# OEMV1_GPS_Interface.net
KiCad netlist of a schematic drawn in EAGLE
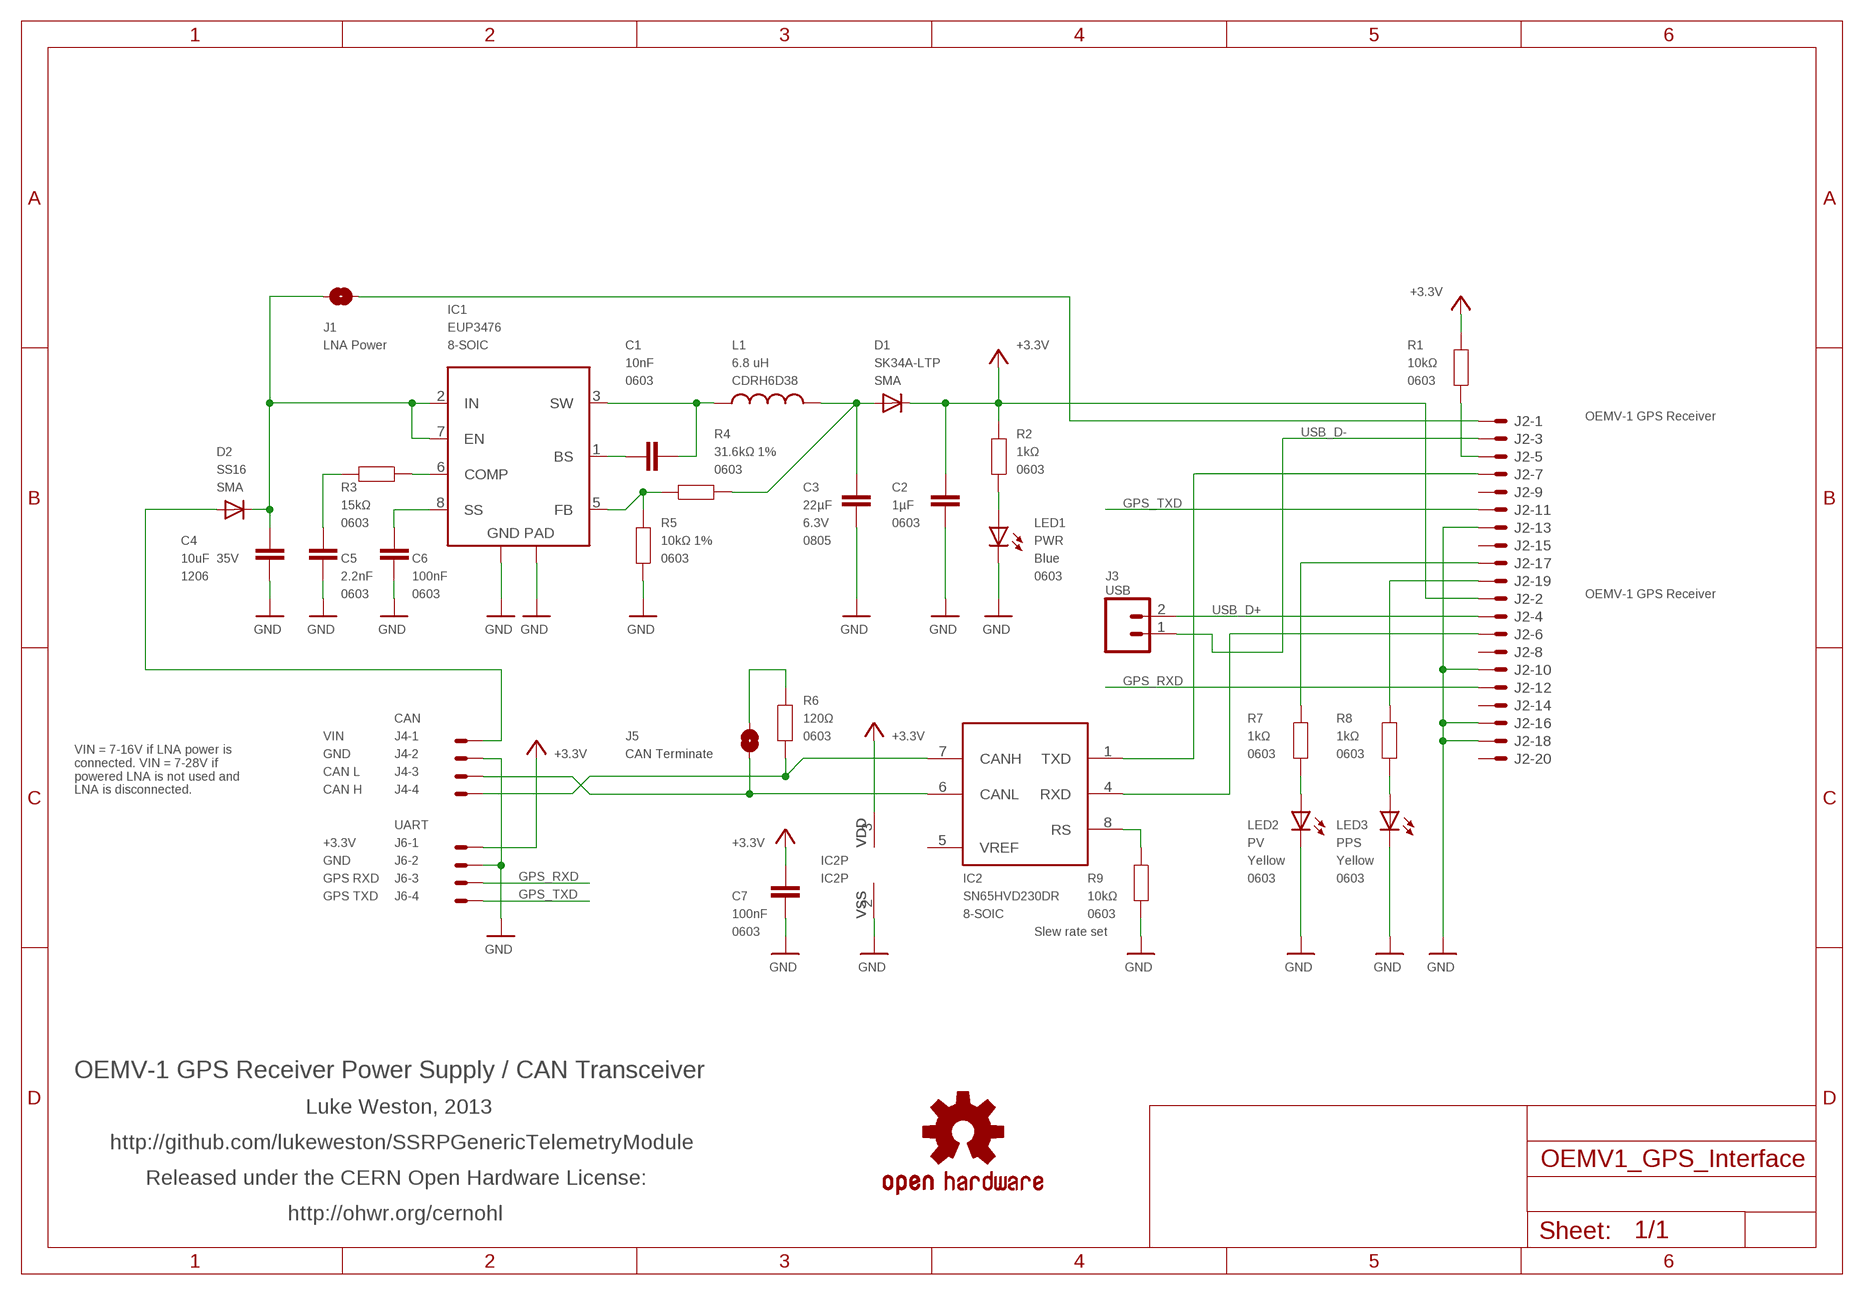
[diagram p0: schematic, sheet 1]

(export (version "E")
  (design (tool "Eeschema 10.0.6"))
  (components
    (comp (ref "C1")
      (value "10nF")
      (footprint "eagle-import:0603")
      (fields (field (name "PACKAGE") "0603"))
      (libsource (lib "eagle-import") (part "CAP0603"))
    )
    (comp (ref "C2")
      (value "1µF")
      (footprint "eagle-import:0603")
      (fields (field (name "PACKAGE") "0603"))
      (libsource (lib "eagle-import") (part "CAP0603"))
    )
    (comp (ref "C3")
      (value "22µF")
      (footprint "eagle-import:0805")
      (fields (field (name "PACKAGE") "0805") (field (name "VOLTAGE") "6.3V"))
      (libsource (lib "eagle-import") (part "CAP0805"))
    )
    (comp (ref "C4")
      (value "10uF")
      (footprint "eagle-import:C1206")
      (fields (field (name "PACKAGE") "1206") (field (name "VOLTAGE") "35V"))
      (libsource (lib "eagle-import") (part "C-EUC1206"))
    )
    (comp (ref "C5")
      (value "2.2nF")
      (footprint "eagle-import:0603")
      (fields (field (name "PACKAGE") "0603"))
      (libsource (lib "eagle-import") (part "CAP0603"))
    )
    (comp (ref "C6")
      (value "100nF")
      (footprint "eagle-import:0603")
      (fields (field (name "PACKAGE") "0603"))
      (libsource (lib "eagle-import") (part "CAP0603"))
    )
    (comp (ref "C7")
      (value "100nF")
      (footprint "eagle-import:0603")
      (fields (field (name "PACKAGE") "0603"))
      (libsource (lib "eagle-import") (part "CAP0603"))
    )
    (comp (ref "D1")
      (value "SK34A-LTP")
      (footprint "eagle-import:SMA-DIODE")
      (fields (field (name "PACKAGE") "SMA"))
      (libsource (lib "eagle-import") (part "DIODESMA"))
    )
    (comp (ref "D2")
      (value "SS16")
      (footprint "eagle-import:SMA-DIODE")
      (fields (field (name "PACKAGE") "SMA"))
      (libsource (lib "eagle-import") (part "DIODESMA"))
    )
    (comp (ref "IC1")
      (value "EUP3476")
      (footprint "eagle-import:SO08T")
      (fields (field (name "PACKAGE") "8-SOIC"))
      (libsource (lib "eagle-import") (part "EUP3476"))
    )
    (comp (ref "IC2")
      (value "SN65HVD230DR")
      (footprint "eagle-import:SO-08")
      (fields (field (name "PACKAGE") "8-SOIC"))
      (libsource (lib "eagle-import") (part "MCP2551SN"))
    )
    (comp (ref "J1")
      (value "LNA Power")
      (footprint "eagle-import:SJ")
      (libsource (lib "eagle-import") (part "SJ"))
    )
    (comp (ref "J2")
      (value "OEMV-1 GPS Receiver")
      (footprint "eagle-import:87758-2016")
      (fields (field (name "MPN") "87758-2016"))
      (libsource (lib "eagle-import") (part "87758-2016"))
    )
    (comp (ref "J3")
      (value "USB")
      (footprint "eagle-import:1X02")
      (libsource (lib "eagle-import") (part "M02PTH"))
    )
    (comp (ref "J4")
      (value "CAN")
      (footprint "eagle-import:22-23-2041")
      (fields (field (name "MF") "MOLEX") (field (name "MPN") "22-23-2041"))
      (libsource (lib "eagle-import") (part "22-23-2041"))
    )
    (comp (ref "J5")
      (value "CAN Terminate")
      (footprint "eagle-import:SJ")
      (libsource (lib "eagle-import") (part "SJ"))
    )
    (comp (ref "J6")
      (value "UART")
      (footprint "eagle-import:22-23-2041")
      (fields (field (name "MF") "MOLEX") (field (name "MPN") "22-23-2041"))
      (libsource (lib "eagle-import") (part "22-23-2041"))
    )
    (comp (ref "L1")
      (value "6.8 uH")
      (footprint "eagle-import:CDRH")
      (fields (field (name "SKU") "CDRH6D38"))
      (libsource (lib "eagle-import") (part "INDUCTOR"))
    )
    (comp (ref "LED1")
      (value "PWR")
      (footprint "eagle-import:LED-0603")
      (fields (field (name "COLOUR") "Blue") (field (name "PACKAGE") "0603"))
      (libsource (lib "eagle-import") (part "LED0603"))
    )
    (comp (ref "LED2")
      (value "PV")
      (footprint "eagle-import:LED-0603")
      (fields (field (name "COLOUR") "Yellow") (field (name "PACKAGE") "0603"))
      (libsource (lib "eagle-import") (part "LED0603"))
    )
    (comp (ref "LED3")
      (value "PPS")
      (footprint "eagle-import:LED-0603")
      (fields (field (name "COLOUR") "Yellow") (field (name "PACKAGE") "0603"))
      (libsource (lib "eagle-import") (part "LED0603"))
    )
    (comp (ref "R1")
      (value "10kΩ")
      (footprint "eagle-import:0603")
      (fields (field (name "PACKAGE") "0603"))
      (libsource (lib "eagle-import") (part "RESISTOR0603"))
    )
    (comp (ref "R2")
      (value "1kΩ")
      (footprint "eagle-import:0603")
      (fields (field (name "PACKAGE") "0603"))
      (libsource (lib "eagle-import") (part "RESISTOR0603"))
    )
    (comp (ref "R3")
      (value "15kΩ")
      (footprint "eagle-import:0603")
      (fields (field (name "PACKAGE") "0603"))
      (libsource (lib "eagle-import") (part "RESISTOR0603"))
    )
    (comp (ref "R4")
      (value "31.6kΩ 1%")
      (footprint "eagle-import:0603")
      (fields (field (name "PACKAGE") "0603"))
      (libsource (lib "eagle-import") (part "RESISTOR0603"))
    )
    (comp (ref "R5")
      (value "10kΩ 1%")
      (footprint "eagle-import:0603")
      (fields (field (name "PACKAGE") "0603"))
      (libsource (lib "eagle-import") (part "RESISTOR0603"))
    )
    (comp (ref "R6")
      (value "120Ω")
      (footprint "eagle-import:0603")
      (fields (field (name "PACKAGE") "0603"))
      (libsource (lib "eagle-import") (part "RESISTOR0603"))
    )
    (comp (ref "R7")
      (value "1kΩ")
      (footprint "eagle-import:0603")
      (fields (field (name "PACKAGE") "0603"))
      (libsource (lib "eagle-import") (part "RESISTOR0603"))
    )
    (comp (ref "R8")
      (value "1kΩ")
      (footprint "eagle-import:0603")
      (fields (field (name "PACKAGE") "0603"))
      (libsource (lib "eagle-import") (part "RESISTOR0603"))
    )
    (comp (ref "R9")
      (value "10kΩ")
      (footprint "eagle-import:0603")
      (fields (field (name "FUNCTION") "Slew rate set") (field (name "PACKAGE") "0603"))
      (libsource (lib "eagle-import") (part "RESISTOR0603"))
    )
    (comp (ref "SY")
      (value "OSHW-LOGOS")
      (footprint "eagle-import:OSHW-LOGO-S")
      (libsource (lib "eagle-import") (part "OSHW-LOGOS"))
    )
  )
  (nets
    (net (code "1") (name "+3.3V") (class "Default")
      (node (ref "C2") (pin "2") (pinfunction "2_2") (pintype "passive"))
      (node (ref "C7") (pin "2") (pinfunction "2_2") (pintype "passive"))
      (node (ref "D1") (pin "C") (pinfunction "C_C") (pintype "passive"))
      (node (ref "IC2") (pin "3") (pinfunction "VDD_3") (pintype "power_in"))
      (node (ref "J2") (pin "2") (pinfunction "S_2") (pintype "passive"))
      (node (ref "J6") (pin "1") (pinfunction "S_1") (pintype "passive"))
      (node (ref "R1") (pin "1") (pinfunction "1_1") (pintype "passive"))
      (node (ref "R2") (pin "1") (pinfunction "1_1") (pintype "passive"))
    )
    (net (code "2") (name "/GPS_RXD") (class "Default")
      (node (ref "J2") (pin "12") (pinfunction "S_12") (pintype "passive"))
      (node (ref "J6") (pin "3") (pinfunction "S_3") (pintype "passive"))
    )
    (net (code "3") (name "/GPS_TXD") (class "Default")
      (node (ref "J2") (pin "11") (pinfunction "S_11") (pintype "passive"))
      (node (ref "J6") (pin "4") (pinfunction "S_4") (pintype "passive"))
    )
    (net (code "4") (name "/USB_D+") (class "Default")
      (node (ref "J2") (pin "4") (pinfunction "S_4") (pintype "passive"))
      (node (ref "J3") (pin "2") (pinfunction "2_2") (pintype "passive"))
    )
    (net (code "5") (name "/USB_D-") (class "Default")
      (node (ref "J2") (pin "3") (pinfunction "S_3") (pintype "passive"))
      (node (ref "J3") (pin "1") (pinfunction "1_1") (pintype "passive"))
    )
    (net (code "6") (name "/VREF") (class "Default")
      (node (ref "IC2") (pin "5") (pinfunction "VREF_5") (pintype "power_in"))
    )
    (net (code "7") (name "GND") (class "Default")
      (node (ref "C2") (pin "1") (pinfunction "1_1") (pintype "passive"))
      (node (ref "C3") (pin "2") (pinfunction "2_2") (pintype "passive"))
      (node (ref "C4") (pin "2") (pinfunction "2_2") (pintype "passive"))
      (node (ref "C5") (pin "1") (pinfunction "1_1") (pintype "passive"))
      (node (ref "C6") (pin "1") (pinfunction "1_1") (pintype "passive"))
      (node (ref "C7") (pin "1") (pinfunction "1_1") (pintype "passive"))
      (node (ref "IC1") (pin "4") (pinfunction "GND_4") (pintype "power_in"))
      (node (ref "IC1") (pin "9") (pinfunction "TGND_9") (pintype "power_in"))
      (node (ref "IC2") (pin "2") (pinfunction "VSS_2") (pintype "power_in"))
      (node (ref "J2") (pin "10") (pinfunction "S_10") (pintype "passive"))
      (node (ref "J2") (pin "13") (pinfunction "S_13") (pintype "passive"))
      (node (ref "J2") (pin "16") (pinfunction "S_16") (pintype "passive"))
      (node (ref "J2") (pin "18") (pinfunction "S_18") (pintype "passive"))
      (node (ref "J4") (pin "2") (pinfunction "S_2") (pintype "passive"))
      (node (ref "J6") (pin "2") (pinfunction "S_2") (pintype "passive"))
      (node (ref "LED1") (pin "C") (pinfunction "C_C") (pintype "passive"))
      (node (ref "LED2") (pin "C") (pinfunction "C_C") (pintype "passive"))
      (node (ref "LED3") (pin "C") (pinfunction "C_C") (pintype "passive"))
      (node (ref "R5") (pin "2") (pinfunction "2_2") (pintype "passive"))
      (node (ref "R9") (pin "2") (pinfunction "2_2") (pintype "passive"))
    )
    (net (code "8") (name "Net-(C3-Pad1)") (class "Default")
      (node (ref "C3") (pin "1") (pinfunction "1_1") (pintype "passive"))
      (node (ref "D1") (pin "A") (pinfunction "A_A") (pintype "passive"))
      (node (ref "L1") (pin "2") (pinfunction "2_2") (pintype "bidirectional"))
      (node (ref "R4") (pin "2") (pinfunction "2_2") (pintype "passive"))
    )
    (net (code "9") (name "Net-(C5-Pad2)") (class "Default")
      (node (ref "C5") (pin "2") (pinfunction "2_2") (pintype "passive"))
      (node (ref "R3") (pin "2") (pinfunction "2_2") (pintype "passive"))
    )
    (net (code "10") (name "Net-(IC1-BS)") (class "Default")
      (node (ref "C1") (pin "2") (pinfunction "2_2") (pintype "passive"))
      (node (ref "IC1") (pin "1") (pinfunction "BS_1") (pintype "bidirectional"))
    )
    (net (code "11") (name "Net-(IC1-COMP)") (class "Default")
      (node (ref "IC1") (pin "6") (pinfunction "COMP_6") (pintype "bidirectional"))
      (node (ref "R3") (pin "1") (pinfunction "1_1") (pintype "passive"))
    )
    (net (code "12") (name "Net-(IC1-EN)") (class "Default")
      (node (ref "C4") (pin "1") (pinfunction "1_1") (pintype "passive"))
      (node (ref "D2") (pin "C") (pinfunction "C_C") (pintype "passive"))
      (node (ref "IC1") (pin "2") (pinfunction "IN_2") (pintype "power_in"))
      (node (ref "IC1") (pin "7") (pinfunction "EN_7") (pintype "input"))
      (node (ref "J1") (pin "1") (pinfunction "1_1") (pintype "passive"))
    )
    (net (code "13") (name "Net-(IC1-FB)") (class "Default")
      (node (ref "IC1") (pin "5") (pinfunction "FB_5") (pintype "bidirectional"))
      (node (ref "R4") (pin "1") (pinfunction "1_1") (pintype "passive"))
      (node (ref "R5") (pin "1") (pinfunction "1_1") (pintype "passive"))
    )
    (net (code "14") (name "Net-(IC1-SS)") (class "Default")
      (node (ref "C6") (pin "2") (pinfunction "2_2") (pintype "passive"))
      (node (ref "IC1") (pin "8") (pinfunction "SS_8") (pintype "bidirectional"))
    )
    (net (code "15") (name "Net-(IC1-SW)") (class "Default")
      (node (ref "C1") (pin "1") (pinfunction "1_1") (pintype "passive"))
      (node (ref "IC1") (pin "3") (pinfunction "SW_3") (pintype "bidirectional"))
      (node (ref "L1") (pin "1") (pinfunction "1_1") (pintype "bidirectional"))
    )
    (net (code "16") (name "Net-(IC2A-CANH)") (class "Default")
      (node (ref "IC2") (pin "7") (pinfunction "CANH_7") (pintype "bidirectional"))
      (node (ref "J4") (pin "4") (pinfunction "S_4") (pintype "passive"))
      (node (ref "R6") (pin "1") (pinfunction "1_1") (pintype "passive"))
    )
    (net (code "17") (name "Net-(IC2A-CANL)") (class "Default")
      (node (ref "IC2") (pin "6") (pinfunction "CANL_6") (pintype "bidirectional"))
      (node (ref "J4") (pin "3") (pinfunction "S_3") (pintype "passive"))
      (node (ref "J5") (pin "2") (pinfunction "2_2") (pintype "passive"))
    )
    (net (code "18") (name "Net-(IC2A-RS)") (class "Default")
      (node (ref "IC2") (pin "8") (pinfunction "RS_8") (pintype "input"))
      (node (ref "R9") (pin "1") (pinfunction "1_1") (pintype "passive"))
    )
    (net (code "19") (name "Net-(IC2A-RXD)") (class "Default")
      (node (ref "IC2") (pin "4") (pinfunction "RXD_4") (pintype "output"))
      (node (ref "J2") (pin "6") (pinfunction "S_6") (pintype "passive"))
    )
    (net (code "20") (name "Net-(IC2A-TXD)") (class "Default")
      (node (ref "IC2") (pin "1") (pinfunction "TXD_1") (pintype "input"))
      (node (ref "J2") (pin "7") (pinfunction "S_7") (pintype "passive"))
    )
    (net (code "21") (name "Net-(J2A-S)") (class "Default")
      (node (ref "J1") (pin "2") (pinfunction "2_2") (pintype "passive"))
      (node (ref "J2") (pin "1") (pinfunction "S_1") (pintype "passive"))
    )
    (net (code "22") (name "Net-(J2I-S)") (class "Default")
      (node (ref "J2") (pin "17") (pinfunction "S_17") (pintype "passive"))
      (node (ref "R7") (pin "2") (pinfunction "2_2") (pintype "passive"))
    )
    (net (code "23") (name "Net-(J2K-S)") (class "Default")
      (node (ref "J2") (pin "19") (pinfunction "S_19") (pintype "passive"))
      (node (ref "R8") (pin "2") (pinfunction "2_2") (pintype "passive"))
    )
    (net (code "24") (name "Net-(J2P-S)") (class "Default")
      (node (ref "J2") (pin "5") (pinfunction "S_5") (pintype "passive"))
      (node (ref "R1") (pin "2") (pinfunction "2_2") (pintype "passive"))
    )
    (net (code "25") (name "Net-(J4A-S)") (class "Default")
      (node (ref "D2") (pin "A") (pinfunction "A_A") (pintype "passive"))
      (node (ref "J4") (pin "1") (pinfunction "S_1") (pintype "passive"))
    )
    (net (code "26") (name "Net-(J5-Pad1)") (class "Default")
      (node (ref "J5") (pin "1") (pinfunction "1_1") (pintype "passive"))
      (node (ref "R6") (pin "2") (pinfunction "2_2") (pintype "passive"))
    )
    (net (code "27") (name "Net-(LED1-PadA)") (class "Default")
      (node (ref "LED1") (pin "A") (pinfunction "A_A") (pintype "passive"))
      (node (ref "R2") (pin "2") (pinfunction "2_2") (pintype "passive"))
    )
    (net (code "28") (name "Net-(LED2-PadA)") (class "Default")
      (node (ref "LED2") (pin "A") (pinfunction "A_A") (pintype "passive"))
      (node (ref "R7") (pin "1") (pinfunction "1_1") (pintype "passive"))
    )
    (net (code "29") (name "Net-(LED3-PadA)") (class "Default")
      (node (ref "LED3") (pin "A") (pinfunction "A_A") (pintype "passive"))
      (node (ref "R8") (pin "1") (pinfunction "1_1") (pintype "passive"))
    )
    (net (code "30") (name "unconnected-(J2F-S-Pad14)") (class "Default")
      (node (ref "J2") (pin "14") (pinfunction "S_14") (pintype "passive"))
    )
    (net (code "31") (name "unconnected-(J2G-S-Pad15)") (class "Default")
      (node (ref "J2") (pin "15") (pinfunction "S_15") (pintype "passive"))
    )
    (net (code "32") (name "unconnected-(J2M-S-Pad20)") (class "Default")
      (node (ref "J2") (pin "20") (pinfunction "S_20") (pintype "passive"))
    )
    (net (code "33") (name "unconnected-(J2S-S-Pad8)") (class "Default")
      (node (ref "J2") (pin "8") (pinfunction "S_8") (pintype "passive"))
    )
    (net (code "34") (name "unconnected-(J2T-S-Pad9)") (class "Default")
      (node (ref "J2") (pin "9") (pinfunction "S_9") (pintype "passive"))
    )
  )
)
